# SecondDriver.net
KiCad netlist of a schematic drawn in Altium Designer
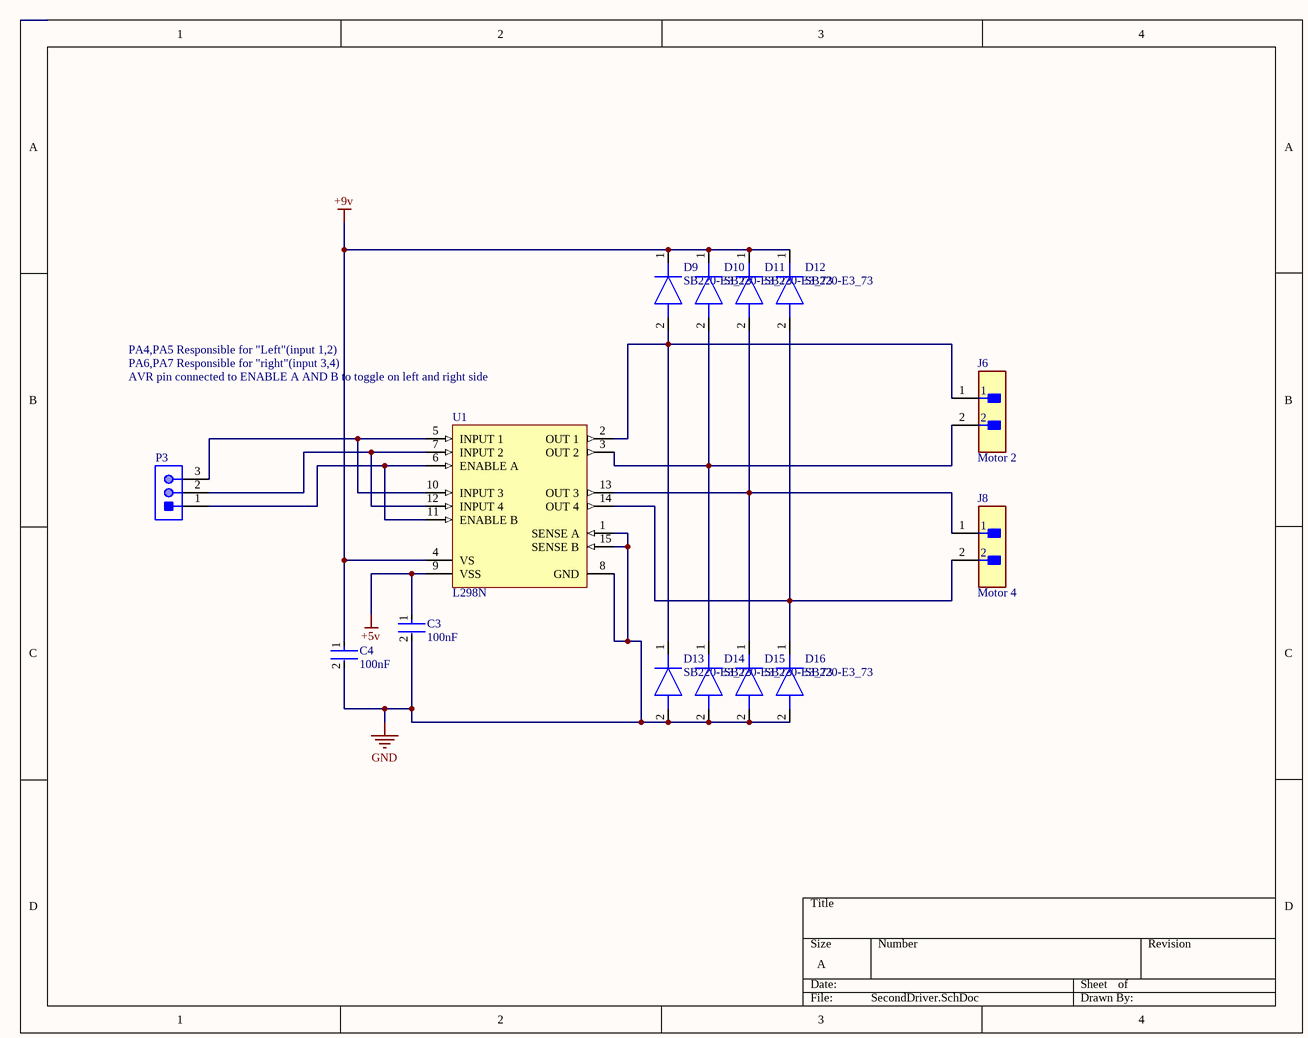
[diagram p0: SecondDriver.SchDoc]

(export (version "E")
  (design (tool "Eeschema 10.0.6"))
  (components
    (comp (ref "C3")
      (value "100nF")
      (footprint "FP-K15H5-MFG")
      (description "CAP CER 0.1UF 50V X7R RADIAL")
      (fields (field (name "TOLERANCE") "10%") (field (name "VOLTAGE") "50V"))
      (libsource (lib "Altium Content Vault") (part "02cd4be3c70576c341d710602a673aa"))
    )
    (comp (ref "C4")
      (value "100nF")
      (footprint "FP-K15H5-MFG")
      (description "CAP CER 0.1UF 50V X7R RADIAL")
      (fields (field (name "TOLERANCE") "10%") (field (name "VOLTAGE") "50V"))
      (libsource (lib "Altium Content Vault") (part "02cd4be3c70576c341d710602a673aa"))
    )
    (comp (ref "D9")
      (value "SB220-E3_73")
      (footprint "SamacSys:DIOAD1910W86L670D310")
      (description "Diode")
      (fields
        (field (name "MANUFACTURER_PART_NUMBER") "SB220-E3/73")
        (field (name "MOUSER PART NUMBER") "625-SB220-E3/73")
      )
      (libsource (lib "*") (part "SB220-E3_73"))
    )
    (comp (ref "D10")
      (value "SB220-E3_73")
      (footprint "SamacSys:DIOAD1910W86L670D310")
      (description "Diode")
      (fields
        (field (name "MANUFACTURER_PART_NUMBER") "SB220-E3/73")
        (field (name "MOUSER PART NUMBER") "625-SB220-E3/73")
      )
      (libsource (lib "*") (part "SB220-E3_73"))
    )
    (comp (ref "D11")
      (value "SB220-E3_73")
      (footprint "SamacSys:DIOAD1910W86L670D310")
      (description "Diode")
      (fields
        (field (name "MANUFACTURER_PART_NUMBER") "SB220-E3/73")
        (field (name "MOUSER PART NUMBER") "625-SB220-E3/73")
      )
      (libsource (lib "*") (part "SB220-E3_73"))
    )
    (comp (ref "D12")
      (value "SB220-E3_73")
      (footprint "SamacSys:DIOAD1910W86L670D310")
      (description "Diode")
      (fields
        (field (name "MANUFACTURER_PART_NUMBER") "SB220-E3/73")
        (field (name "MOUSER PART NUMBER") "625-SB220-E3/73")
      )
      (libsource (lib "*") (part "SB220-E3_73"))
    )
    (comp (ref "D13")
      (value "SB220-E3_73")
      (footprint "SamacSys:DIOAD1910W86L670D310")
      (description "Diode")
      (fields
        (field (name "MANUFACTURER_PART_NUMBER") "SB220-E3/73")
        (field (name "MOUSER PART NUMBER") "625-SB220-E3/73")
      )
      (libsource (lib "*") (part "SB220-E3_73"))
    )
    (comp (ref "D14")
      (value "SB220-E3_73")
      (footprint "SamacSys:DIOAD1910W86L670D310")
      (description "Diode")
      (fields
        (field (name "MANUFACTURER_PART_NUMBER") "SB220-E3/73")
        (field (name "MOUSER PART NUMBER") "625-SB220-E3/73")
      )
      (libsource (lib "*") (part "SB220-E3_73"))
    )
    (comp (ref "D15")
      (value "SB220-E3_73")
      (footprint "SamacSys:DIOAD1910W86L670D310")
      (description "Diode")
      (fields
        (field (name "MANUFACTURER_PART_NUMBER") "SB220-E3/73")
        (field (name "MOUSER PART NUMBER") "625-SB220-E3/73")
      )
      (libsource (lib "*") (part "SB220-E3_73"))
    )
    (comp (ref "D16")
      (value "SB220-E3_73")
      (footprint "SamacSys:DIOAD1910W86L670D310")
      (description "Diode")
      (fields
        (field (name "MANUFACTURER_PART_NUMBER") "SB220-E3/73")
        (field (name "MOUSER PART NUMBER") "625-SB220-E3/73")
      )
      (libsource (lib "*") (part "SB220-E3_73"))
    )
    (comp (ref "J6")
      (value "Motor 2")
      (footprint "FP-M20-9990246-MFG")
      (description "CONN HEADER VERT 2POS 2.54MM")
      (fields
        (field (name "OCTOPART") "https://octopart.com/m20-9990246-harwin-2590635")
        (field (name "MANUFACTURER") "Harwin")
      )
      (libsource (lib "Altium Content Vault") (part "3bc925449376181038e59eaffc5286c"))
    )
    (comp (ref "J8")
      (value "Motor 4")
      (footprint "FP-M20-9990246-MFG")
      (description "CONN HEADER VERT 2POS 2.54MM")
      (fields
        (field (name "OCTOPART") "https://octopart.com/m20-9990246-harwin-2590635")
        (field (name "MANUFACTURER") "Harwin")
      )
      (libsource (lib "Altium Content Vault") (part "3bc925449376181038e59eaffc5286c"))
    )
    (comp (ref "P3")
      (value "~")
      (footprint "MOLX-22-28-4033_V")
      (description "Male Header, Pitch 2.54 mm, 1 x 3 Position, Height 8.38 mm, Tail Length 3.18 mm, RoHS, Bulk")
      (fields (field (name "MANUFACTURER") "Molex"))
      (libsource (lib "Altium Content Vault") (part "CN-1P-M-R3"))
    )
    (comp (ref "U1")
      (value "L298N")
      (footprint "STM-FM-15")
      (description "Dual Full-Bridge Driver, 4.8 to 46 V, -40 to 150 degC, 15-Pin FM (MW 15L), RoHS, Tube")
      (fields (field (name "MANUFACTURER") "STMicroelectronics") (field (name "PARTNUMBER") "L298"))
      (libsource (lib "Altium Content Vault") (part "STM-L298-15"))
    )
  )
  (nets
    (net (code "1") (name "+5v") (class "Default")
      (node (ref "C3") (pin "1") (pinfunction "1_1") (pintype "passive"))
      (node (ref "U1") (pin "9") (pinfunction "VSS_9") (pintype "power_in"))
    )
    (net (code "2") (name "+9v") (class "Default")
      (node (ref "C4") (pin "1") (pinfunction "1_1") (pintype "passive"))
      (node (ref "D10") (pin "1") (pinfunction "K_1") (pintype "passive"))
      (node (ref "D11") (pin "1") (pinfunction "K_1") (pintype "passive"))
      (node (ref "D12") (pin "1") (pinfunction "K_1") (pintype "passive"))
      (node (ref "D9") (pin "1") (pinfunction "K_1") (pintype "passive"))
      (node (ref "U1") (pin "4") (pinfunction "VS_4") (pintype "power_in"))
    )
    (net (code "3") (name "GND") (class "Default")
      (node (ref "C3") (pin "2") (pinfunction "2_2") (pintype "passive"))
      (node (ref "C4") (pin "2") (pinfunction "2_2") (pintype "passive"))
      (node (ref "D13") (pin "2") (pinfunction "A_2") (pintype "passive"))
      (node (ref "D14") (pin "2") (pinfunction "A_2") (pintype "passive"))
      (node (ref "D15") (pin "2") (pinfunction "A_2") (pintype "passive"))
      (node (ref "D16") (pin "2") (pinfunction "A_2") (pintype "passive"))
      (node (ref "U1") (pin "1") (pinfunction "SENSE_A_1") (pintype "input"))
      (node (ref "U1") (pin "15") (pinfunction "SENSE_B_15") (pintype "input"))
      (node (ref "U1") (pin "8") (pinfunction "GND_8") (pintype "power_in"))
    )
    (net (code "4") (name "Net-(D10-A)") (class "Default")
      (node (ref "D10") (pin "2") (pinfunction "A_2") (pintype "passive"))
      (node (ref "D14") (pin "1") (pinfunction "K_1") (pintype "passive"))
      (node (ref "J6") (pin "2") (pinfunction "2_2") (pintype "passive"))
      (node (ref "U1") (pin "3") (pinfunction "OUT_2_3") (pintype "output"))
    )
    (net (code "5") (name "Net-(D11-A)") (class "Default")
      (node (ref "D11") (pin "2") (pinfunction "A_2") (pintype "passive"))
      (node (ref "D15") (pin "1") (pinfunction "K_1") (pintype "passive"))
      (node (ref "J8") (pin "1") (pinfunction "1_1") (pintype "passive"))
      (node (ref "U1") (pin "13") (pinfunction "OUT_3_13") (pintype "output"))
    )
    (net (code "6") (name "Net-(D12-A)") (class "Default")
      (node (ref "D12") (pin "2") (pinfunction "A_2") (pintype "passive"))
      (node (ref "D16") (pin "1") (pinfunction "K_1") (pintype "passive"))
      (node (ref "J8") (pin "2") (pinfunction "2_2") (pintype "passive"))
      (node (ref "U1") (pin "14") (pinfunction "OUT_4_14") (pintype "output"))
    )
    (net (code "7") (name "Net-(D13-K)") (class "Default")
      (node (ref "D13") (pin "1") (pinfunction "K_1") (pintype "passive"))
      (node (ref "D9") (pin "2") (pinfunction "A_2") (pintype "passive"))
      (node (ref "J6") (pin "1") (pinfunction "1_1") (pintype "passive"))
      (node (ref "U1") (pin "2") (pinfunction "OUT_1_2") (pintype "output"))
    )
    (net (code "8") (name "Net-(U1-ENABLE_A)") (class "Default")
      (node (ref "P3") (pin "1") (pinfunction "1_1") (pintype "passive"))
      (node (ref "U1") (pin "11") (pinfunction "ENABLE_B_11") (pintype "input"))
      (node (ref "U1") (pin "6") (pinfunction "ENABLE_A_6") (pintype "input"))
    )
    (net (code "9") (name "Net-(U1-INPUT_1)") (class "Default")
      (node (ref "P3") (pin "3") (pinfunction "3_3") (pintype "passive"))
      (node (ref "U1") (pin "10") (pinfunction "INPUT_3_10") (pintype "input"))
      (node (ref "U1") (pin "5") (pinfunction "INPUT_1_5") (pintype "input"))
    )
    (net (code "10") (name "Net-(U1-INPUT_2)") (class "Default")
      (node (ref "P3") (pin "2") (pinfunction "2_2") (pintype "passive"))
      (node (ref "U1") (pin "12") (pinfunction "INPUT_4_12") (pintype "input"))
      (node (ref "U1") (pin "7") (pinfunction "INPUT_2_7") (pintype "input"))
    )
  )
)
